# part_1.net
KiCad netlist of a schematic drawn in Altium Designer
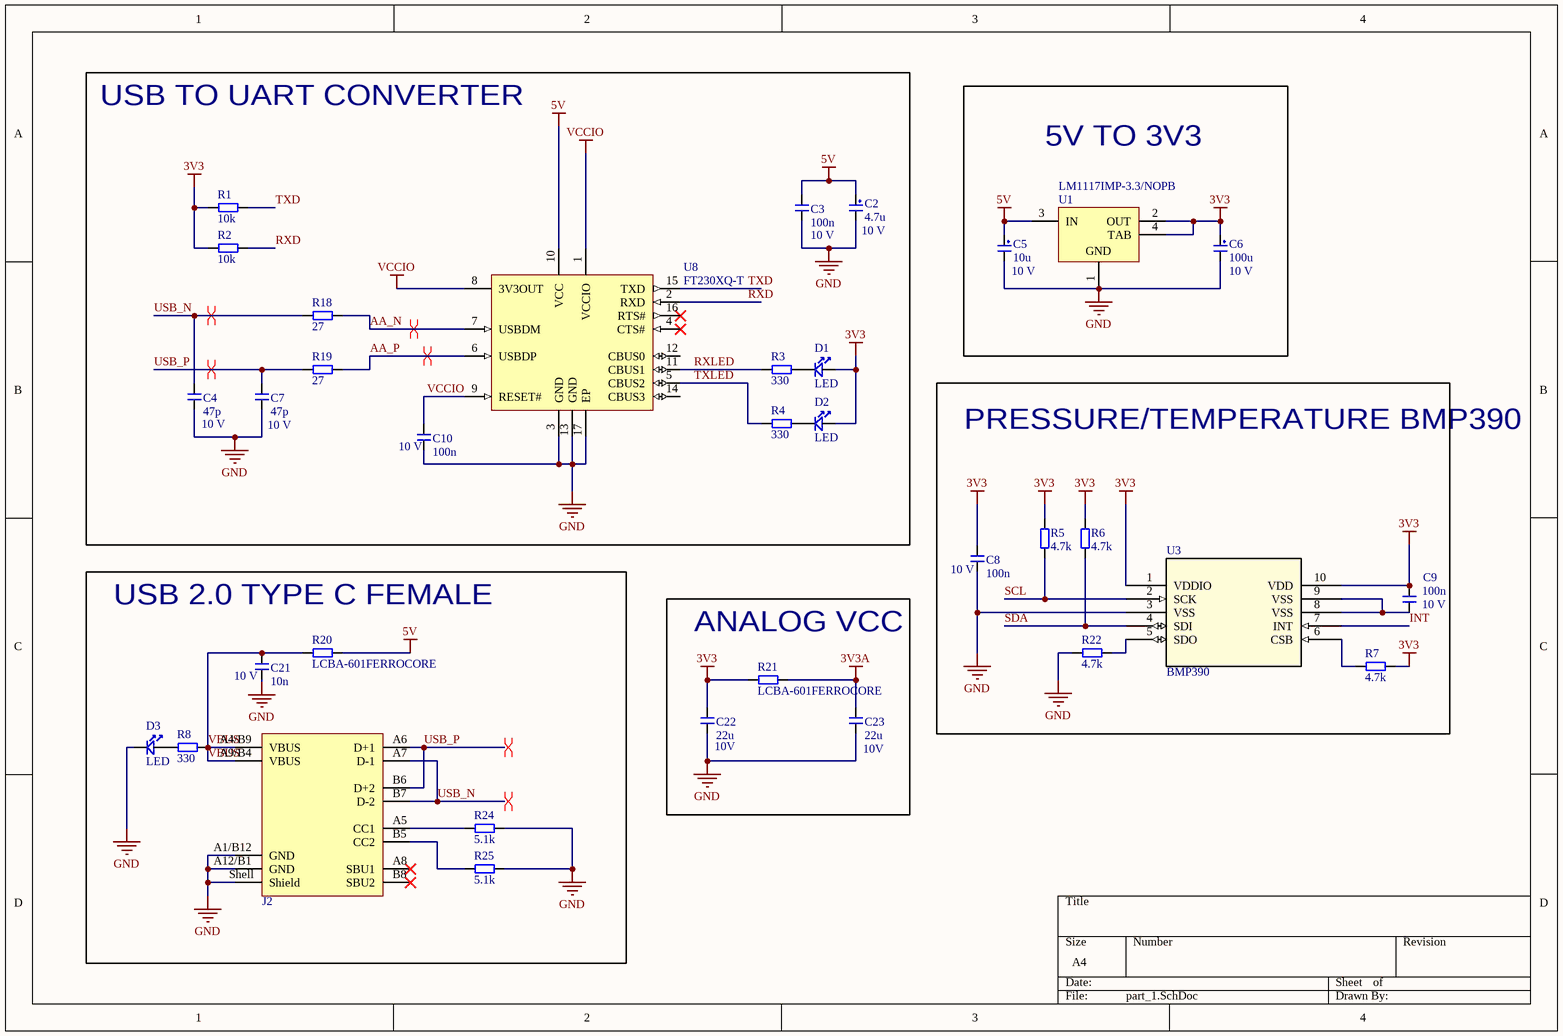
[diagram p0: part_1.SchDoc]

(export (version "E")
  (design (tool "Eeschema 10.0.6"))
  (components
    (comp (ref "C2")
      (value "4.7u")
      (footprint "TANT_A")
      (description "kondensator tantalowy")
      (fields (field (name "VOLTAGE") "10 V"))
      (libsource (lib "ETR-rozne") (part "CapP"))
    )
    (comp (ref "C3")
      (value "100n")
      (footprint "0603")
      (description "kondensator ceramiczny")
      (fields (field (name "V") "10 V") (field (name "VOLTAGE") "10 V"))
      (libsource (lib "ETR-rozne") (part "CapN"))
    )
    (comp (ref "C4")
      (value "47p")
      (footprint "0603")
      (description "kondensator ceramiczny")
      (fields (field (name "VOLTAGE") "10 V"))
      (libsource (lib "ETR-rozne") (part "CapN"))
    )
    (comp (ref "C5")
      (value "10u")
      (footprint "TANT_A")
      (description "kondensator tantalowy")
      (fields (field (name "VOLTAGE") "10 V"))
      (libsource (lib "ETR-rozne") (part "CapP"))
    )
    (comp (ref "C6")
      (value "100u")
      (footprint "TANT_A")
      (description "kondensator tantalowy")
      (fields (field (name "VOLTAGE") "10 V"))
      (libsource (lib "ETR-rozne") (part "CapP"))
    )
    (comp (ref "C7")
      (value "47p")
      (footprint "0603")
      (description "kondensator ceramiczny")
      (fields (field (name "VOLTAGE") "10 V"))
      (libsource (lib "ETR-rozne") (part "CapN"))
    )
    (comp (ref "C8")
      (value "100n")
      (footprint "0603")
      (description "kondensator ceramiczny")
      (fields (field (name "V") "10 V") (field (name "VOLTAGE") "10 V"))
      (libsource (lib "ETR-rozne") (part "CapN"))
    )
    (comp (ref "C9")
      (value "100n")
      (footprint "0603")
      (description "kondensator ceramiczny")
      (fields (field (name "V") "10 V") (field (name "VOLTAGE") "10 V"))
      (libsource (lib "ETR-rozne") (part "CapN"))
    )
    (comp (ref "C10")
      (value "100n")
      (footprint "0603")
      (description "kondensator ceramiczny")
      (fields (field (name "V") "10 V") (field (name "VOLTAGE") "10 V"))
      (libsource (lib "ETR-rozne") (part "CapN"))
    )
    (comp (ref "C21")
      (value "10n")
      (footprint "0603")
      (description "kondensator ceramiczny")
      (fields (field (name "VOLTAGE") "10 V"))
      (libsource (lib "ETR-rozne") (part "CapN"))
    )
    (comp (ref "C22")
      (value "22u")
      (footprint "0603")
      (description "kondensator ceramiczny")
      (fields (field (name "V") "10V"))
      (libsource (lib "ETR-rozne") (part "CapN"))
    )
    (comp (ref "C23")
      (value "22u")
      (footprint "0603")
      (description "kondensator ceramiczny")
      (fields (field (name "V") "10V"))
      (libsource (lib "ETR-rozne") (part "CapN"))
    )
    (comp (ref "D1")
      (value "LED")
      (footprint "Dioda_0805")
      (description "Dioda LED SMD")
      (libsource (lib "ETR-rozne") (part "Dioda_LED"))
    )
    (comp (ref "D2")
      (value "LED")
      (footprint "Dioda_0805")
      (description "Dioda LED SMD")
      (libsource (lib "ETR-rozne") (part "Dioda_LED"))
    )
    (comp (ref "D3")
      (value "LED")
      (footprint "Dioda_0805")
      (description "Dioda LED SMD")
      (libsource (lib "ETR-rozne") (part "Dioda_LED"))
    )
    (comp (ref "J2")
      (value "629722000214")
      (footprint "629722000214")
      (description "WR-COM USB 2.0 Type C Receptacle Horizontal SMT")
      (fields (field (name "MANUFACTURER") "Wurth Elektronik"))
      (libsource (lib "Altium_WR-USB (rev24b)") (part "629722000214"))
    )
    (comp (ref "R1")
      (value "10k")
      (footprint "0603")
      (description "Rezystor SMD")
      (libsource (lib "ETR-rozne") (part "Res"))
    )
    (comp (ref "R2")
      (value "10k")
      (footprint "0603")
      (description "Rezystor SMD")
      (libsource (lib "ETR-rozne") (part "Res"))
    )
    (comp (ref "R3")
      (value "330")
      (footprint "0603")
      (description "Rezystor SMD")
      (libsource (lib "ETR-rozne") (part "Res"))
    )
    (comp (ref "R4")
      (value "330")
      (footprint "0603")
      (description "Rezystor SMD")
      (libsource (lib "ETR-rozne") (part "Res"))
    )
    (comp (ref "R5")
      (value "4.7k")
      (footprint "0603")
      (description "Rezystor SMD")
      (libsource (lib "ETR-rozne") (part "Res"))
    )
    (comp (ref "R6")
      (value "4.7k")
      (footprint "0603")
      (description "Rezystor SMD")
      (libsource (lib "ETR-rozne") (part "Res"))
    )
    (comp (ref "R7")
      (value "4.7k")
      (footprint "0603")
      (description "Rezystor SMD")
      (libsource (lib "ETR-rozne") (part "Res"))
    )
    (comp (ref "R8")
      (value "330")
      (footprint "0603")
      (description "Rezystor SMD")
      (libsource (lib "ETR-rozne") (part "Res"))
    )
    (comp (ref "R18")
      (value "27")
      (footprint "0603")
      (description "Rezystor SMD")
      (libsource (lib "ETR-rozne") (part "Res"))
    )
    (comp (ref "R19")
      (value "27")
      (footprint "0603")
      (description "Rezystor SMD")
      (libsource (lib "ETR-rozne") (part "Res"))
    )
    (comp (ref "R20")
      (value "LCBA-601FERROCORE")
      (footprint "0402")
      (description "Rezystor SMD")
      (libsource (lib "ETR-rozne") (part "Res"))
    )
    (comp (ref "R21")
      (value "LCBA-601FERROCORE")
      (footprint "0402")
      (description "Rezystor SMD")
      (libsource (lib "ETR-rozne") (part "Res"))
    )
    (comp (ref "R22")
      (value "4.7k")
      (footprint "0603")
      (description "Rezystor SMD")
      (libsource (lib "ETR-rozne") (part "Res"))
    )
    (comp (ref "R24")
      (value "5.1k")
      (footprint "0402")
      (description "Rezystor SMD")
      (libsource (lib "ETR-rozne") (part "Res"))
    )
    (comp (ref "R25")
      (value "5.1k")
      (footprint "0402")
      (description "Rezystor SMD")
      (libsource (lib "ETR-rozne") (part "Res"))
    )
    (comp (ref "U1")
      (value "LM1117IMP-3.3/NOPB")
      (footprint "DCY0004A_N")
      (description "800mA Low-Dropout Linear Regulator, 4-pin SOT-223, Pb-Free")
      (fields (field (name "MANUFACTURER") "Texas Instruments"))
      (libsource (lib "Altium Content Vault") (part "PM-REG-LM1086-SOT4"))
    )
    (comp (ref "U3")
      (value "BMP390")
      (footprint "10LGA_2X2X0p75_BOS")
      (description "No Description Available")
      (libsource (lib "BMP390") (part "BMP390"))
    )
    (comp (ref "U8")
      (value "FT230XQ-T")
      (footprint "QFN-16_N")
      (fields (field (name "MANUFACTURER") "FTDI"))
      (libsource (lib "ETR-rozne") (part "FT230XQ-T"))
    )
  )
  (nets
    (net (code "1") (name "/AA_N") (class "Default")
      (node (ref "R18") (pin "1") (pinfunction "1_1") (pintype "passive"))
      (node (ref "U8") (pin "7") (pinfunction "USBDM_7") (pintype "input"))
    )
    (net (code "2") (name "/AA_P") (class "Default")
      (node (ref "R19") (pin "1") (pinfunction "1_1") (pintype "passive"))
      (node (ref "U8") (pin "6") (pinfunction "USBDP_6") (pintype "input"))
    )
    (net (code "3") (name "/INT") (class "Default")
      (node (ref "U3") (pin "7") (pinfunction "INT_7") (pintype "input"))
    )
    (net (code "4") (name "/RXD") (class "Default")
      (node (ref "R2") (pin "1") (pinfunction "1_1") (pintype "passive"))
      (node (ref "U8") (pin "2") (pinfunction "RXD_2") (pintype "input"))
    )
    (net (code "5") (name "/RXLED") (class "Default")
      (node (ref "R3") (pin "1") (pinfunction "1_1") (pintype "passive"))
      (node (ref "U8") (pin "11") (pinfunction "CBUS1_11") (pintype "bidirectional"))
    )
    (net (code "6") (name "/SCL") (class "Default")
      (node (ref "R5") (pin "1") (pinfunction "1_1") (pintype "passive"))
      (node (ref "U3") (pin "2") (pinfunction "SCK_2") (pintype "input"))
    )
    (net (code "7") (name "/SDA") (class "Default")
      (node (ref "R6") (pin "1") (pinfunction "1_1") (pintype "passive"))
      (node (ref "U3") (pin "4") (pinfunction "SDI_4") (pintype "bidirectional"))
    )
    (net (code "8") (name "/TXD") (class "Default")
      (node (ref "R1") (pin "1") (pinfunction "1_1") (pintype "passive"))
      (node (ref "U8") (pin "15") (pinfunction "TXD_15") (pintype "output"))
    )
    (net (code "9") (name "/TXLED") (class "Default")
      (node (ref "R4") (pin "1") (pinfunction "1_1") (pintype "passive"))
      (node (ref "U8") (pin "5") (pinfunction "CBUS2_5") (pintype "bidirectional"))
    )
    (net (code "10") (name "/USB_N") (class "Default")
      (node (ref "C4") (pin "2") (pinfunction "2_2") (pintype "passive"))
      (node (ref "J2") (pin "A7") (pinfunction "D-1_A7") (pintype "passive"))
      (node (ref "J2") (pin "B7") (pinfunction "D-2_B7") (pintype "passive"))
      (node (ref "R18") (pin "2") (pinfunction "2_2") (pintype "passive"))
    )
    (net (code "11") (name "/USB_P") (class "Default")
      (node (ref "C7") (pin "2") (pinfunction "2_2") (pintype "passive"))
      (node (ref "J2") (pin "A6") (pinfunction "D+1_A6") (pintype "passive"))
      (node (ref "J2") (pin "B6") (pinfunction "D+2_B6") (pintype "passive"))
      (node (ref "R19") (pin "2") (pinfunction "2_2") (pintype "passive"))
    )
    (net (code "12") (name "/VBUS") (class "Default")
      (node (ref "C21") (pin "2") (pinfunction "2_2") (pintype "passive"))
      (node (ref "J2") (pin "A4/B9") (pinfunction "VBUS_A4/B9") (pintype "passive"))
      (node (ref "J2") (pin "A9/B4") (pinfunction "VBUS_A9/B4") (pintype "passive"))
      (node (ref "R20") (pin "1") (pinfunction "1_1") (pintype "passive"))
      (node (ref "R8") (pin "1") (pinfunction "1_1") (pintype "passive"))
    )
    (net (code "13") (name "3V3") (class "Default")
      (node (ref "C22") (pin "2") (pinfunction "2_2") (pintype "passive"))
      (node (ref "C6") (pin "1") (pinfunction "1_1") (pintype "passive"))
      (node (ref "C8") (pin "2") (pinfunction "2_2") (pintype "passive"))
      (node (ref "C9") (pin "2") (pinfunction "2_2") (pintype "passive"))
      (node (ref "D1") (pin "2") (pinfunction "2_2") (pintype "passive"))
      (node (ref "D2") (pin "2") (pinfunction "2_2") (pintype "passive"))
      (node (ref "R1") (pin "2") (pinfunction "2_2") (pintype "passive"))
      (node (ref "R2") (pin "2") (pinfunction "2_2") (pintype "passive"))
      (node (ref "R21") (pin "1") (pinfunction "1_1") (pintype "passive"))
      (node (ref "R5") (pin "2") (pinfunction "2_2") (pintype "passive"))
      (node (ref "R6") (pin "2") (pinfunction "2_2") (pintype "passive"))
      (node (ref "R7") (pin "2") (pinfunction "2_2") (pintype "passive"))
      (node (ref "U1") (pin "2") (pinfunction "OUT_2") (pintype "power_in"))
      (node (ref "U1") (pin "4") (pinfunction "TAB_4") (pintype "power_in"))
      (node (ref "U3") (pin "1") (pinfunction "VDDIO_1") (pintype "power_in"))
      (node (ref "U3") (pin "10") (pinfunction "VDD_10") (pintype "power_in"))
    )
    (net (code "14") (name "3V3A") (class "Default")
      (node (ref "C23") (pin "2") (pinfunction "2_2") (pintype "passive"))
      (node (ref "R21") (pin "2") (pinfunction "2_2") (pintype "passive"))
    )
    (net (code "15") (name "5V") (class "Default")
      (node (ref "C2") (pin "1") (pinfunction "1_1") (pintype "passive"))
      (node (ref "C3") (pin "2") (pinfunction "2_2") (pintype "passive"))
      (node (ref "C5") (pin "1") (pinfunction "1_1") (pintype "passive"))
      (node (ref "R20") (pin "2") (pinfunction "2_2") (pintype "passive"))
      (node (ref "U1") (pin "3") (pinfunction "IN_3") (pintype "power_in"))
      (node (ref "U8") (pin "10") (pinfunction "VCC_10") (pintype "power_in"))
    )
    (net (code "16") (name "GND") (class "Default")
      (node (ref "C10") (pin "1") (pinfunction "1_1") (pintype "passive"))
      (node (ref "C2") (pin "2") (pinfunction "2_2") (pintype "passive"))
      (node (ref "C21") (pin "1") (pinfunction "1_1") (pintype "passive"))
      (node (ref "C22") (pin "1") (pinfunction "1_1") (pintype "passive"))
      (node (ref "C23") (pin "1") (pinfunction "1_1") (pintype "passive"))
      (node (ref "C3") (pin "1") (pinfunction "1_1") (pintype "passive"))
      (node (ref "C4") (pin "1") (pinfunction "1_1") (pintype "passive"))
      (node (ref "C5") (pin "2") (pinfunction "2_2") (pintype "passive"))
      (node (ref "C6") (pin "2") (pinfunction "2_2") (pintype "passive"))
      (node (ref "C7") (pin "1") (pinfunction "1_1") (pintype "passive"))
      (node (ref "C8") (pin "1") (pinfunction "1_1") (pintype "passive"))
      (node (ref "D3") (pin "1") (pinfunction "1_1") (pintype "passive"))
      (node (ref "J2") (pin "A1/B12") (pinfunction "GND_A1/B12") (pintype "passive"))
      (node (ref "J2") (pin "A12/B1") (pinfunction "GND_A12/B1") (pintype "passive"))
      (node (ref "J2") (pin "Shell") (pinfunction "Shield_Shell") (pintype "passive"))
      (node (ref "R22") (pin "1") (pinfunction "1_1") (pintype "passive"))
      (node (ref "R24") (pin "2") (pinfunction "2_2") (pintype "passive"))
      (node (ref "R25") (pin "2") (pinfunction "2_2") (pintype "passive"))
      (node (ref "U1") (pin "1") (pinfunction "GND_1") (pintype "power_in"))
      (node (ref "U3") (pin "3") (pinfunction "VSS_3") (pintype "power_in"))
      (node (ref "U8") (pin "13") (pinfunction "GND_13") (pintype "power_in"))
      (node (ref "U8") (pin "17") (pinfunction "EP_17") (pintype "power_in"))
      (node (ref "U8") (pin "3") (pinfunction "GND_3") (pintype "power_in"))
    )
    (net (code "17") (name "Net-(C9-Pad1)") (class "Default")
      (node (ref "C9") (pin "1") (pinfunction "1_1") (pintype "passive"))
      (node (ref "U3") (pin "8") (pinfunction "VSS_8") (pintype "power_in"))
      (node (ref "U3") (pin "9") (pinfunction "VSS_9") (pintype "power_in"))
    )
    (net (code "18") (name "Net-(D1-Pad1)") (class "Default")
      (node (ref "D1") (pin "1") (pinfunction "1_1") (pintype "passive"))
      (node (ref "R3") (pin "2") (pinfunction "2_2") (pintype "passive"))
    )
    (net (code "19") (name "Net-(D2-Pad1)") (class "Default")
      (node (ref "D2") (pin "1") (pinfunction "1_1") (pintype "passive"))
      (node (ref "R4") (pin "2") (pinfunction "2_2") (pintype "passive"))
    )
    (net (code "20") (name "Net-(D3-Pad2)") (class "Default")
      (node (ref "D3") (pin "2") (pinfunction "2_2") (pintype "passive"))
      (node (ref "R8") (pin "2") (pinfunction "2_2") (pintype "passive"))
    )
    (net (code "21") (name "Net-(J2-CC1)") (class "Default")
      (node (ref "J2") (pin "A5") (pinfunction "CC1_A5") (pintype "passive"))
      (node (ref "R24") (pin "1") (pinfunction "1_1") (pintype "passive"))
    )
    (net (code "22") (name "Net-(J2-CC2)") (class "Default")
      (node (ref "J2") (pin "B5") (pinfunction "CC2_B5") (pintype "passive"))
      (node (ref "R25") (pin "1") (pinfunction "1_1") (pintype "passive"))
    )
    (net (code "23") (name "Net-(U3-CSB)") (class "Default")
      (node (ref "R7") (pin "1") (pinfunction "1_1") (pintype "passive"))
      (node (ref "U3") (pin "6") (pinfunction "CSB_6") (pintype "input"))
    )
    (net (code "24") (name "Net-(U3-SDO)") (class "Default")
      (node (ref "R22") (pin "2") (pinfunction "2_2") (pintype "passive"))
      (node (ref "U3") (pin "5") (pinfunction "SDO_5") (pintype "bidirectional"))
    )
    (net (code "25") (name "VCCIO") (class "Default")
      (node (ref "C10") (pin "2") (pinfunction "2_2") (pintype "passive"))
      (node (ref "U8") (pin "1") (pinfunction "VCCIO_1") (pintype "power_in"))
      (node (ref "U8") (pin "8") (pinfunction "3V3OUT_8") (pintype "power_in"))
      (node (ref "U8") (pin "9") (pinfunction "RESET#_9") (pintype "input"))
    )
    (net (code "26") (name "unconnected-(J2-SBU1-PadA8)") (class "Default")
      (node (ref "J2") (pin "A8") (pinfunction "SBU1_A8") (pintype "passive+no_connect"))
    )
    (net (code "27") (name "unconnected-(J2-SBU2-PadB8)") (class "Default")
      (node (ref "J2") (pin "B8") (pinfunction "SBU2_B8") (pintype "passive+no_connect"))
    )
    (net (code "28") (name "unconnected-(U8-CBUS0-Pad12)") (class "Default")
      (node (ref "U8") (pin "12") (pinfunction "CBUS0_12") (pintype "bidirectional"))
    )
    (net (code "29") (name "unconnected-(U8-CBUS3-Pad14)") (class "Default")
      (node (ref "U8") (pin "14") (pinfunction "CBUS3_14") (pintype "bidirectional"))
    )
    (net (code "30") (name "unconnected-(U8-CTS#-Pad4)") (class "Default")
      (node (ref "U8") (pin "4") (pinfunction "CTS#_4") (pintype "input+no_connect"))
    )
    (net (code "31") (name "unconnected-(U8-RTS#-Pad16)") (class "Default")
      (node (ref "U8") (pin "16") (pinfunction "RTS#_16") (pintype "output+no_connect"))
    )
  )
)
